# Power.net
KiCad netlist of a schematic drawn in Altium Designer
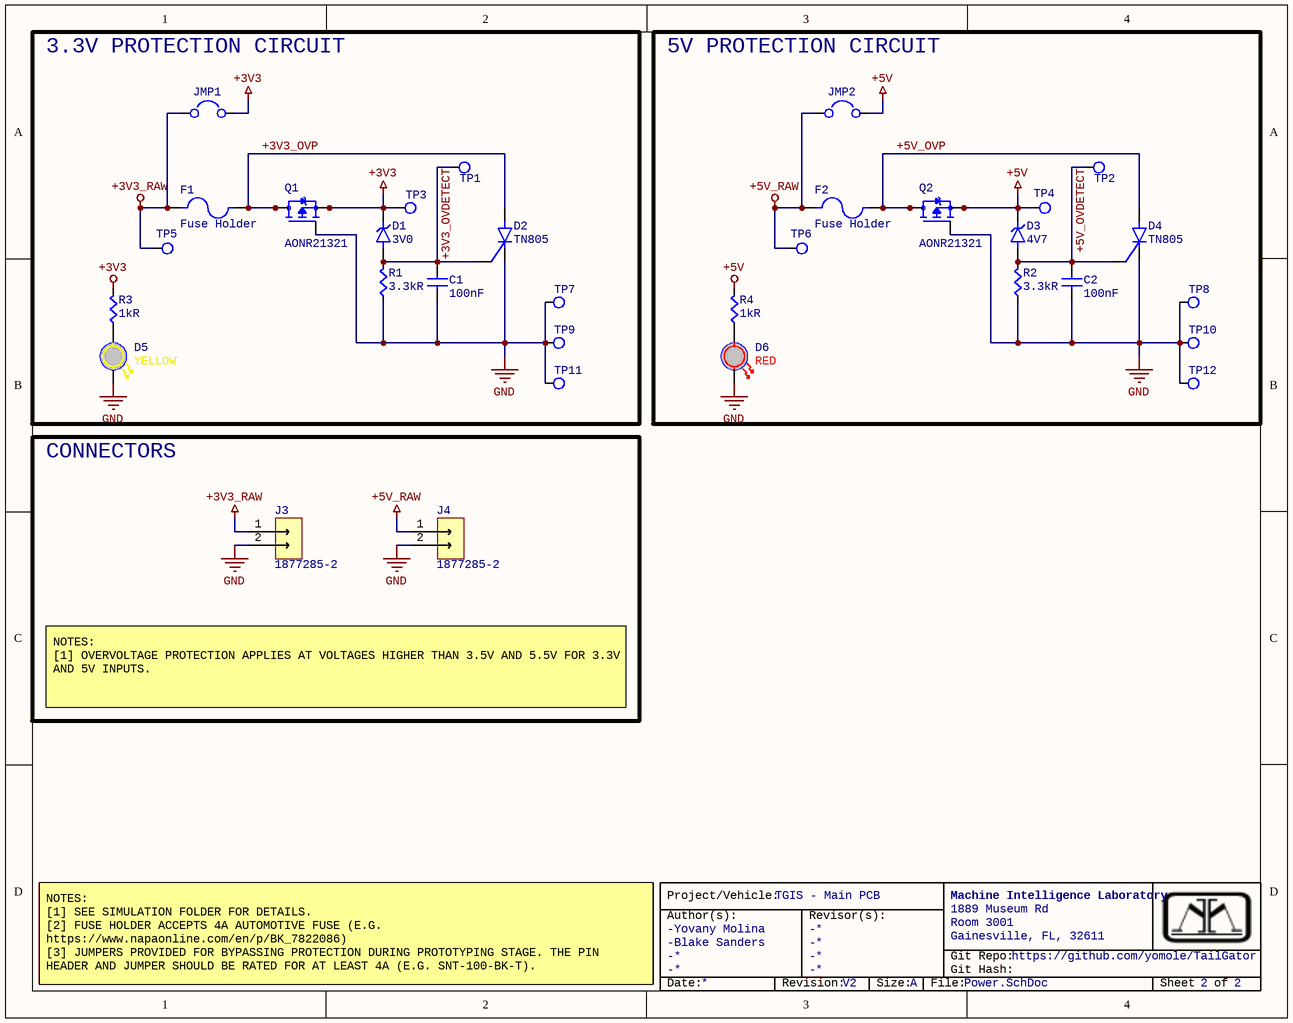
[diagram p0: Power.SchDoc]

(export (version "E")
  (design (tool "Eeschema 10.0.6"))
  (components
    (comp (ref "C1")
      (value "100nF")
      (footprint "CAPC0603")
      (description "Ceramic Capacitor, Multilayer, Cera")
      (fields (field (name "PART NUMBER") "CC0603KRX7R7BB104") (field (name "MANUFACTURER") "Yageo"))
      (libsource (lib "Parts") (part "NP_Capacitor"))
    )
    (comp (ref "C2")
      (value "100nF")
      (footprint "CAPC0603")
      (description "Ceramic Capacitor, Multilayer, Cera")
      (fields (field (name "PART NUMBER") "CC0603KRX7R7BB104") (field (name "MANUFACTURER") "Yageo"))
      (libsource (lib "Parts") (part "NP_Capacitor"))
    )
    (comp (ref "D1")
      (value "3V0")
      (footprint "SOD3715X135N")
      (description "DIODE ZENER 3.0V 500MW SOD123")
      (fields (field (name "MP") "BZT52C4V7S R9") (field (name "MF") "Taiwan Semiconductor"))
      (libsource (lib "TGIS_Power") (part "BZT52C3V0"))
    )
    (comp (ref "D2")
      (value "TN805")
      (footprint "DPAK_TN")
      (description "SCR 600 V 8 A Standard Recovery Surface Mount DPAK")
      (fields (field (name "MP") "BZT52C4V7S R9") (field (name "MF") "Taiwan Semiconductor"))
      (libsource (lib "TGIS_Power") (part "TN805-600B-TR"))
    )
    (comp (ref "D3")
      (value "4V7")
      (footprint "SOD3715X135N")
      (description "DIODE ZENER 4.7V 500MW SOD123")
      (fields (field (name "MP") "BZT52C4V7S R9") (field (name "MF") "Taiwan Semiconductor"))
      (libsource (lib "TGIS") (part "BZT52C4V7"))
    )
    (comp (ref "D4")
      (value "TN805")
      (footprint "DPAK_TN")
      (description "SCR 600 V 8 A Standard Recovery Surface Mount DPAK")
      (fields (field (name "MP") "BZT52C4V7S R9") (field (name "MF") "Taiwan Semiconductor"))
      (libsource (lib "TGIS_Power") (part "TN805-600B-TR"))
    )
    (comp (ref "D5")
      (value "YELLOW")
      (footprint "LED0603")
      (description "Single Color LED, Yellow, Water Cle")
      (fields (field (name "PART NUMBER") "150060YS75000") (field (name "MANUFACTURER") "Wurth Electronics"))
      (libsource (lib "Parts") (part "LED_Yellow"))
    )
    (comp (ref "D6")
      (value "RED")
      (footprint "LED0603")
      (description "Single Color LED, Red, Water Clear,")
      (fields (field (name "PART NUMBER") "150060RS75000") (field (name "MANUFACTURER") "Wurth Electronics"))
      (libsource (lib "Parts") (part "LED_Red"))
    )
    (comp (ref "F1")
      (value "Fuse Holder")
      (footprint "FUSE_3568")
      (description "Fuse Holder 30 A 500V 1 Circuit Blade Through Hole")
      (fields (field (name "MP") "3568"))
      (libsource (lib "TGIS_Power") (part "3568"))
    )
    (comp (ref "F2")
      (value "Fuse Holder")
      (footprint "FUSE_3568")
      (description "Fuse Holder 30 A 500V 1 Circuit Blade Through Hole")
      (fields (field (name "MP") "3568"))
      (libsource (lib "TGIS_Power") (part "3568"))
    )
    (comp (ref "J3")
      (value "1877285-2")
      (footprint "TE_1877285-2")
      (libsource (lib "TGIS_Connectors") (part "1877285-2"))
    )
    (comp (ref "J4")
      (value "1877285-2")
      (footprint "TE_1877285-2")
      (libsource (lib "TGIS_Connectors") (part "1877285-2"))
    )
    (comp (ref "JMP1")
      (value "2PINJUMPER")
      (footprint "2PinJumper")
      (description "2 Position Jumper")
      (libsource (lib "TGIS_Connectors") (part "2PINJUMPER"))
    )
    (comp (ref "JMP2")
      (value "2PINJUMPER")
      (footprint "2PinJumper")
      (description "2 Position Jumper")
      (libsource (lib "TGIS_Connectors") (part "2PINJUMPER"))
    )
    (comp (ref "Q1")
      (value "AONR21321")
      (footprint "TRANS_AONR21321")
      (description "P-Channel 30 V 24A (Tc) 4.1W (Ta), 24W (Tc) Surface Mount 8-DFN-EP (3x3)")
      (fields (field (name "MF") "Alpha &"))
      (libsource (lib "TGIS_Power") (part "AONR21321"))
    )
    (comp (ref "Q2")
      (value "AONR21321")
      (footprint "TRANS_AONR21321")
      (description "P-Channel 30 V 24A (Tc) 4.1W (Ta), 24W (Tc) Surface Mount 8-DFN-EP (3x3)")
      (fields (field (name "MF") "Alpha &"))
      (libsource (lib "TGIS_Power") (part "AONR21321"))
    )
    (comp (ref "R1")
      (value "3.3kR")
      (footprint "RES0603")
      (description "Fixed Resistor, Metal Glaze/thick F")
      (fields (field (name "PART NUMBER") "RC0603FR-073K3L") (field (name "POWER") "100mW"))
      (libsource (lib "Parts") (part "Resistor"))
    )
    (comp (ref "R2")
      (value "3.3kR")
      (footprint "RES0603")
      (description "Fixed Resistor, Metal Glaze/thick F")
      (fields (field (name "PART NUMBER") "RC0603FR-073K3L") (field (name "POWER") "100mW"))
      (libsource (lib "Parts") (part "Resistor"))
    )
    (comp (ref "R3")
      (value "1kR")
      (footprint "RES0603")
      (description "Fixed Resistor, Metal Glaze/thick F")
      (fields (field (name "PART NUMBER") "RC0603FR-071KL") (field (name "POWER") "100mW"))
      (libsource (lib "Parts") (part "Resistor"))
    )
    (comp (ref "R4")
      (value "1kR")
      (footprint "RES0603")
      (description "Fixed Resistor, Metal Glaze/thick F")
      (fields (field (name "PART NUMBER") "RC0603FR-071KL") (field (name "POWER") "100mW"))
      (libsource (lib "Parts") (part "Resistor"))
    )
    (comp (ref "TP1") (value "TP") (footprint "TPTH-100mil") (libsource (lib "TGIS") (part "TP")))
    (comp (ref "TP2") (value "TP") (footprint "TPTH-100mil") (libsource (lib "TGIS") (part "TP")))
    (comp (ref "TP3") (value "TP") (footprint "TPTH-100mil") (libsource (lib "TGIS") (part "TP")))
    (comp (ref "TP4") (value "TP") (footprint "TPTH-100mil") (libsource (lib "TGIS_Connectors") (part "TP")))
    (comp (ref "TP5") (value "TP") (footprint "TPTH-100mil") (libsource (lib "TGIS_Connectors") (part "TP")))
    (comp (ref "TP6") (value "TP") (footprint "TPTH-100mil") (libsource (lib "TGIS_Connectors") (part "TP")))
    (comp (ref "TP7") (value "TP") (footprint "TPTH-100mil") (libsource (lib "TGIS") (part "TP")))
    (comp (ref "TP8") (value "TP") (footprint "TPTH-100mil") (libsource (lib "TGIS") (part "TP")))
    (comp (ref "TP9") (value "TP") (footprint "TPTH-100mil") (libsource (lib "TGIS") (part "TP")))
    (comp (ref "TP10") (value "TP") (footprint "TPTH-100mil") (libsource (lib "TGIS") (part "TP")))
    (comp (ref "TP11") (value "TP") (footprint "TPTH-100mil") (libsource (lib "TGIS") (part "TP")))
    (comp (ref "TP12") (value "TP") (footprint "TPTH-100mil") (libsource (lib "TGIS") (part "TP")))
  )
  (nets
    (net (code "1") (name "+3V3") (class "Default")
      (node (ref "D1") (pin "K") (pinfunction "K_K") (pintype "passive"))
      (node (ref "JMP1") (pin "2") (pinfunction "2_2") (pintype "passive"))
      (node (ref "Q1") (pin "1") (pinfunction "S_1") (pintype "passive"))
      (node (ref "Q1") (pin "2") (pinfunction "S_2") (pintype "passive"))
      (node (ref "Q1") (pin "3") (pinfunction "S_3") (pintype "passive"))
      (node (ref "R3") (pin "1") (pinfunction "A_1") (pintype "passive"))
      (node (ref "TP3") (pin "1") (pinfunction "1_1") (pintype "passive"))
    )
    (net (code "2") (name "+3V3_RAW") (class "Default")
      (node (ref "F1") (pin "1") (pinfunction "1_1") (pintype "passive"))
      (node (ref "F1") (pin "3") (pinfunction "1_3") (pintype "passive"))
      (node (ref "J3") (pin "1") (pinfunction "1_1") (pintype "passive"))
      (node (ref "JMP1") (pin "1") (pinfunction "1_1") (pintype "passive"))
      (node (ref "TP5") (pin "1") (pinfunction "1_1") (pintype "passive"))
    )
    (net (code "3") (name "+5V") (class "Default")
      (node (ref "D3") (pin "K") (pinfunction "K_K") (pintype "passive"))
      (node (ref "JMP2") (pin "2") (pinfunction "2_2") (pintype "passive"))
      (node (ref "Q2") (pin "1") (pinfunction "S_1") (pintype "passive"))
      (node (ref "Q2") (pin "2") (pinfunction "S_2") (pintype "passive"))
      (node (ref "Q2") (pin "3") (pinfunction "S_3") (pintype "passive"))
      (node (ref "R4") (pin "1") (pinfunction "A_1") (pintype "passive"))
      (node (ref "TP4") (pin "1") (pinfunction "1_1") (pintype "passive"))
    )
    (net (code "4") (name "+5V_RAW") (class "Default")
      (node (ref "F2") (pin "1") (pinfunction "1_1") (pintype "passive"))
      (node (ref "F2") (pin "3") (pinfunction "1_3") (pintype "passive"))
      (node (ref "J4") (pin "1") (pinfunction "1_1") (pintype "passive"))
      (node (ref "JMP2") (pin "1") (pinfunction "1_1") (pintype "passive"))
      (node (ref "TP6") (pin "1") (pinfunction "1_1") (pintype "passive"))
    )
    (net (code "5") (name "/+3V3_OVDETECT") (class "Default")
      (node (ref "C1") (pin "1") (pinfunction "A_1") (pintype "passive"))
      (node (ref "D1") (pin "A") (pinfunction "A_A") (pintype "passive"))
      (node (ref "D2") (pin "G") (pinfunction "G_G") (pintype "passive"))
      (node (ref "R1") (pin "1") (pinfunction "A_1") (pintype "passive"))
      (node (ref "TP1") (pin "1") (pinfunction "1_1") (pintype "passive"))
    )
    (net (code "6") (name "/+3V3_OVP") (class "Default")
      (node (ref "D2") (pin "A") (pinfunction "A_A") (pintype "passive"))
      (node (ref "F1") (pin "2") (pinfunction "2_2") (pintype "passive"))
      (node (ref "F1") (pin "4") (pinfunction "2_4") (pintype "passive"))
      (node (ref "Q1") (pin "5") (pinfunction "D_5") (pintype "passive"))
      (node (ref "Q1") (pin "6") (pinfunction "D_6") (pintype "passive"))
      (node (ref "Q1") (pin "7") (pinfunction "D_7") (pintype "passive"))
      (node (ref "Q1") (pin "8") (pinfunction "D_8") (pintype "passive"))
      (node (ref "Q1") (pin "9") (pinfunction "D_9") (pintype "passive"))
      (node (ref "Q1") (pin "9_1") (pinfunction "D_9_1") (pintype "passive"))
      (node (ref "Q1") (pin "9_2") (pinfunction "D_9_2") (pintype "passive"))
    )
    (net (code "7") (name "/+5V_OVDETECT") (class "Default")
      (node (ref "C2") (pin "1") (pinfunction "A_1") (pintype "passive"))
      (node (ref "D3") (pin "A") (pinfunction "A_A") (pintype "passive"))
      (node (ref "D4") (pin "G") (pinfunction "G_G") (pintype "passive"))
      (node (ref "R2") (pin "1") (pinfunction "A_1") (pintype "passive"))
      (node (ref "TP2") (pin "1") (pinfunction "1_1") (pintype "passive"))
    )
    (net (code "8") (name "/+5V_OVP") (class "Default")
      (node (ref "D4") (pin "A") (pinfunction "A_A") (pintype "passive"))
      (node (ref "F2") (pin "2") (pinfunction "2_2") (pintype "passive"))
      (node (ref "F2") (pin "4") (pinfunction "2_4") (pintype "passive"))
      (node (ref "Q2") (pin "5") (pinfunction "D_5") (pintype "passive"))
      (node (ref "Q2") (pin "6") (pinfunction "D_6") (pintype "passive"))
      (node (ref "Q2") (pin "7") (pinfunction "D_7") (pintype "passive"))
      (node (ref "Q2") (pin "8") (pinfunction "D_8") (pintype "passive"))
      (node (ref "Q2") (pin "9") (pinfunction "D_9") (pintype "passive"))
      (node (ref "Q2") (pin "9_1") (pinfunction "D_9_1") (pintype "passive"))
      (node (ref "Q2") (pin "9_2") (pinfunction "D_9_2") (pintype "passive"))
    )
    (net (code "9") (name "GND") (class "Default")
      (node (ref "C1") (pin "2") (pinfunction "B_2") (pintype "passive"))
      (node (ref "C2") (pin "2") (pinfunction "B_2") (pintype "passive"))
      (node (ref "D2") (pin "K") (pinfunction "K_K") (pintype "passive"))
      (node (ref "D4") (pin "K") (pinfunction "K_K") (pintype "passive"))
      (node (ref "D5") (pin "C") (pinfunction "C_C") (pintype "passive"))
      (node (ref "D6") (pin "C") (pinfunction "C_C") (pintype "passive"))
      (node (ref "J3") (pin "2") (pinfunction "2_2") (pintype "passive"))
      (node (ref "J4") (pin "2") (pinfunction "2_2") (pintype "passive"))
      (node (ref "Q1") (pin "4") (pinfunction "G_4") (pintype "passive"))
      (node (ref "Q2") (pin "4") (pinfunction "G_4") (pintype "passive"))
      (node (ref "R1") (pin "2") (pinfunction "B_2") (pintype "passive"))
      (node (ref "R2") (pin "2") (pinfunction "B_2") (pintype "passive"))
      (node (ref "TP10") (pin "1") (pinfunction "1_1") (pintype "passive"))
      (node (ref "TP11") (pin "1") (pinfunction "1_1") (pintype "passive"))
      (node (ref "TP12") (pin "1") (pinfunction "1_1") (pintype "passive"))
      (node (ref "TP7") (pin "1") (pinfunction "1_1") (pintype "passive"))
      (node (ref "TP8") (pin "1") (pinfunction "1_1") (pintype "passive"))
      (node (ref "TP9") (pin "1") (pinfunction "1_1") (pintype "passive"))
    )
    (net (code "10") (name "Net-(R3-B)") (class "Default")
      (node (ref "D5") (pin "A") (pinfunction "A_A") (pintype "passive"))
      (node (ref "R3") (pin "2") (pinfunction "B_2") (pintype "passive"))
    )
    (net (code "11") (name "Net-(R4-B)") (class "Default")
      (node (ref "D6") (pin "A") (pinfunction "A_A") (pintype "passive"))
      (node (ref "R4") (pin "2") (pinfunction "B_2") (pintype "passive"))
    )
  )
)
